# 12vand9v.net
KiCad netlist of a schematic drawn in EAGLE
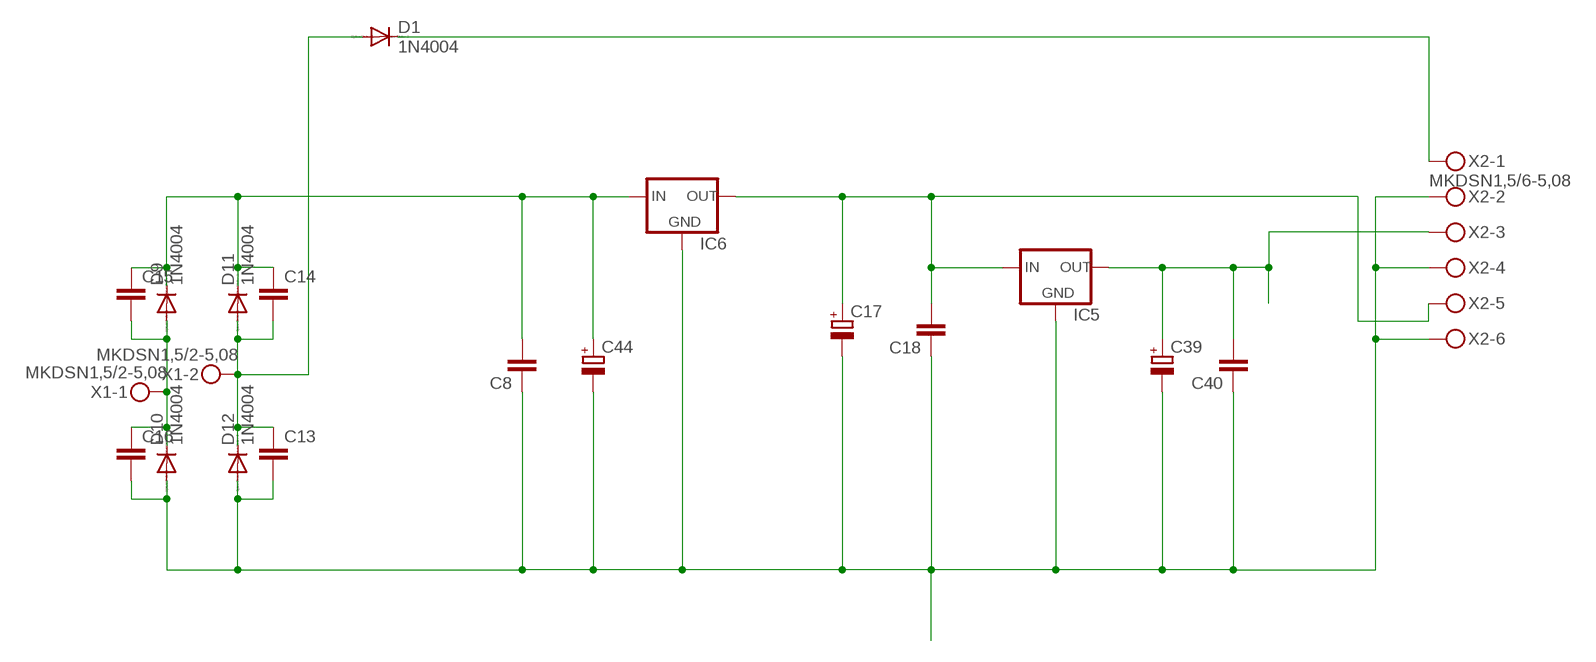
[diagram p0: schematic, sheet 1]

(export (version "E")
  (design (tool "Eeschema 10.0.6"))
  (components
    (comp (ref "C8")
      (value "C-EU050-045X075")
      (footprint "eagle-import:C050-045X075")
      (libsource (lib "eagle-import") (part "C-EU050-045X075"))
    )
    (comp (ref "C13")
      (value "C-EU025-025X050")
      (footprint "eagle-import:C025-025X050")
      (libsource (lib "eagle-import") (part "C-EU025-025X050"))
    )
    (comp (ref "C14")
      (value "C-EU025-025X050")
      (footprint "eagle-import:C025-025X050")
      (libsource (lib "eagle-import") (part "C-EU025-025X050"))
    )
    (comp (ref "C15")
      (value "C-EU025-025X050")
      (footprint "eagle-import:C025-025X050")
      (libsource (lib "eagle-import") (part "C-EU025-025X050"))
    )
    (comp (ref "C16")
      (value "C-EU025-025X050")
      (footprint "eagle-import:C025-025X050")
      (libsource (lib "eagle-import") (part "C-EU025-025X050"))
    )
    (comp (ref "C17")
      (value "CPOL-EUE5-10.5")
      (footprint "eagle-import:E5-10,5")
      (libsource (lib "eagle-import") (part "CPOL-EUE5-10.5"))
    )
    (comp (ref "C18")
      (value "C-EU050-045X075")
      (footprint "eagle-import:C050-045X075")
      (libsource (lib "eagle-import") (part "C-EU050-045X075"))
    )
    (comp (ref "C39")
      (value "CPOL-EUE5-10.5")
      (footprint "eagle-import:E5-10,5")
      (libsource (lib "eagle-import") (part "CPOL-EUE5-10.5"))
    )
    (comp (ref "C40")
      (value "C-EU050-045X075")
      (footprint "eagle-import:C050-045X075")
      (libsource (lib "eagle-import") (part "C-EU050-045X075"))
    )
    (comp (ref "C44")
      (value "CPOL-EUE7.5-18")
      (footprint "eagle-import:E7,5-18")
      (libsource (lib "eagle-import") (part "CPOL-EUE7.5-18"))
    )
    (comp (ref "D1")
      (value "1N4004")
      (footprint "eagle-import:DO41-10")
      (libsource (lib "eagle-import") (part "1N4004"))
    )
    (comp (ref "D9")
      (value "1N4004")
      (footprint "eagle-import:DO41-10")
      (libsource (lib "eagle-import") (part "1N4004"))
    )
    (comp (ref "D10")
      (value "1N4004")
      (footprint "eagle-import:DO41-10")
      (libsource (lib "eagle-import") (part "1N4004"))
    )
    (comp (ref "D11")
      (value "1N4004")
      (footprint "eagle-import:DO41-10")
      (libsource (lib "eagle-import") (part "1N4004"))
    )
    (comp (ref "D12")
      (value "1N4004")
      (footprint "eagle-import:DO41-10")
      (libsource (lib "eagle-import") (part "1N4004"))
    )
    (comp (ref "IC5")
      (value "78XXS")
      (footprint "eagle-import:78XXS")
      (libsource (lib "eagle-import") (part "78XXS"))
    )
    (comp (ref "IC6")
      (value "78XXS")
      (footprint "eagle-import:78XXS")
      (libsource (lib "eagle-import") (part "78XXS"))
    )
    (comp (ref "X1")
      (value "MKDSN1,5/2-5,08")
      (footprint "eagle-import:MKDSN1,5_2-5,08")
      (libsource (lib "eagle-import") (part "MKDSN1,5/2-5,08"))
    )
    (comp (ref "X2")
      (value "MKDSN1,5/6-5,08")
      (footprint "eagle-import:MKDSN1,5_6-5,08")
      (libsource (lib "eagle-import") (part "MKDSN1,5/6-5,08"))
    )
  )
  (nets
    (net (code "1") (name "Net-(C14-Pad1)") (class "Default")
      (node (ref "C14") (pin "1") (pinfunction "1_1") (pintype "passive"))
      (node (ref "C15") (pin "1") (pinfunction "1_1") (pintype "passive"))
      (node (ref "C44") (pin "+") (pinfunction "+_+") (pintype "passive"))
      (node (ref "C8") (pin "2") (pinfunction "2_2") (pintype "passive"))
      (node (ref "D11") (pin "C") (pinfunction "C_C") (pintype "passive"))
      (node (ref "D9") (pin "C") (pinfunction "C_C") (pintype "passive"))
      (node (ref "IC6") (pin "IN") (pinfunction "IN_IN") (pintype "input"))
    )
    (net (code "2") (name "Net-(X1A-KL)") (class "Default")
      (node (ref "C15") (pin "2") (pinfunction "2_2") (pintype "passive"))
      (node (ref "C16") (pin "1") (pinfunction "1_1") (pintype "passive"))
      (node (ref "D10") (pin "C") (pinfunction "C_C") (pintype "passive"))
      (node (ref "D9") (pin "A") (pinfunction "A_A") (pintype "passive"))
      (node (ref "X1") (pin "1") (pinfunction "KL_1") (pintype "passive"))
    )
    (net (code "3") (name "Net-(X1B-KL)") (class "Default")
      (node (ref "C13") (pin "1") (pinfunction "1_1") (pintype "passive"))
      (node (ref "C14") (pin "2") (pinfunction "2_2") (pintype "passive"))
      (node (ref "D1") (pin "A") (pinfunction "A_A") (pintype "passive"))
      (node (ref "D11") (pin "A") (pinfunction "A_A") (pintype "passive"))
      (node (ref "D12") (pin "C") (pinfunction "C_C") (pintype "passive"))
      (node (ref "X1") (pin "2") (pinfunction "KL_2") (pintype "passive"))
    )
    (net (code "4") (name "Net-(X2A-KL)") (class "Default")
      (node (ref "D1") (pin "C") (pinfunction "C_C") (pintype "passive"))
      (node (ref "X2") (pin "1") (pinfunction "KL_1") (pintype "passive"))
    )
    (net (code "5") (name "Net-(X2B-KL)") (class "Default")
      (node (ref "C13") (pin "2") (pinfunction "2_2") (pintype "passive"))
      (node (ref "C16") (pin "2") (pinfunction "2_2") (pintype "passive"))
      (node (ref "C17") (pin "-") (pinfunction "-_-") (pintype "passive"))
      (node (ref "C18") (pin "1") (pinfunction "1_1") (pintype "passive"))
      (node (ref "C39") (pin "-") (pinfunction "-_-") (pintype "passive"))
      (node (ref "C40") (pin "1") (pinfunction "1_1") (pintype "passive"))
      (node (ref "C44") (pin "-") (pinfunction "-_-") (pintype "passive"))
      (node (ref "C8") (pin "1") (pinfunction "1_1") (pintype "passive"))
      (node (ref "D10") (pin "A") (pinfunction "A_A") (pintype "passive"))
      (node (ref "D12") (pin "A") (pinfunction "A_A") (pintype "passive"))
      (node (ref "IC5") (pin "GND") (pinfunction "GND_GND") (pintype "input"))
      (node (ref "IC6") (pin "GND") (pinfunction "GND_GND") (pintype "input"))
      (node (ref "X2") (pin "2") (pinfunction "KL_2") (pintype "passive"))
      (node (ref "X2") (pin "4") (pinfunction "KL_4") (pintype "passive"))
      (node (ref "X2") (pin "6") (pinfunction "KL_6") (pintype "passive"))
    )
    (net (code "6") (name "Net-(X2C-KL)") (class "Default")
      (node (ref "C39") (pin "+") (pinfunction "+_+") (pintype "passive"))
      (node (ref "C40") (pin "2") (pinfunction "2_2") (pintype "passive"))
      (node (ref "IC5") (pin "OUT") (pinfunction "OUT_OUT") (pintype "passive"))
      (node (ref "X2") (pin "3") (pinfunction "KL_3") (pintype "passive"))
    )
    (net (code "7") (name "Net-(X2E-KL)") (class "Default")
      (node (ref "C17") (pin "+") (pinfunction "+_+") (pintype "passive"))
      (node (ref "C18") (pin "2") (pinfunction "2_2") (pintype "passive"))
      (node (ref "IC5") (pin "IN") (pinfunction "IN_IN") (pintype "input"))
      (node (ref "IC6") (pin "OUT") (pinfunction "OUT_OUT") (pintype "passive"))
      (node (ref "X2") (pin "5") (pinfunction "KL_5") (pintype "passive"))
    )
  )
)
